# ADC_Sergeant.net
KiCad netlist of a schematic drawn in Altium Designer
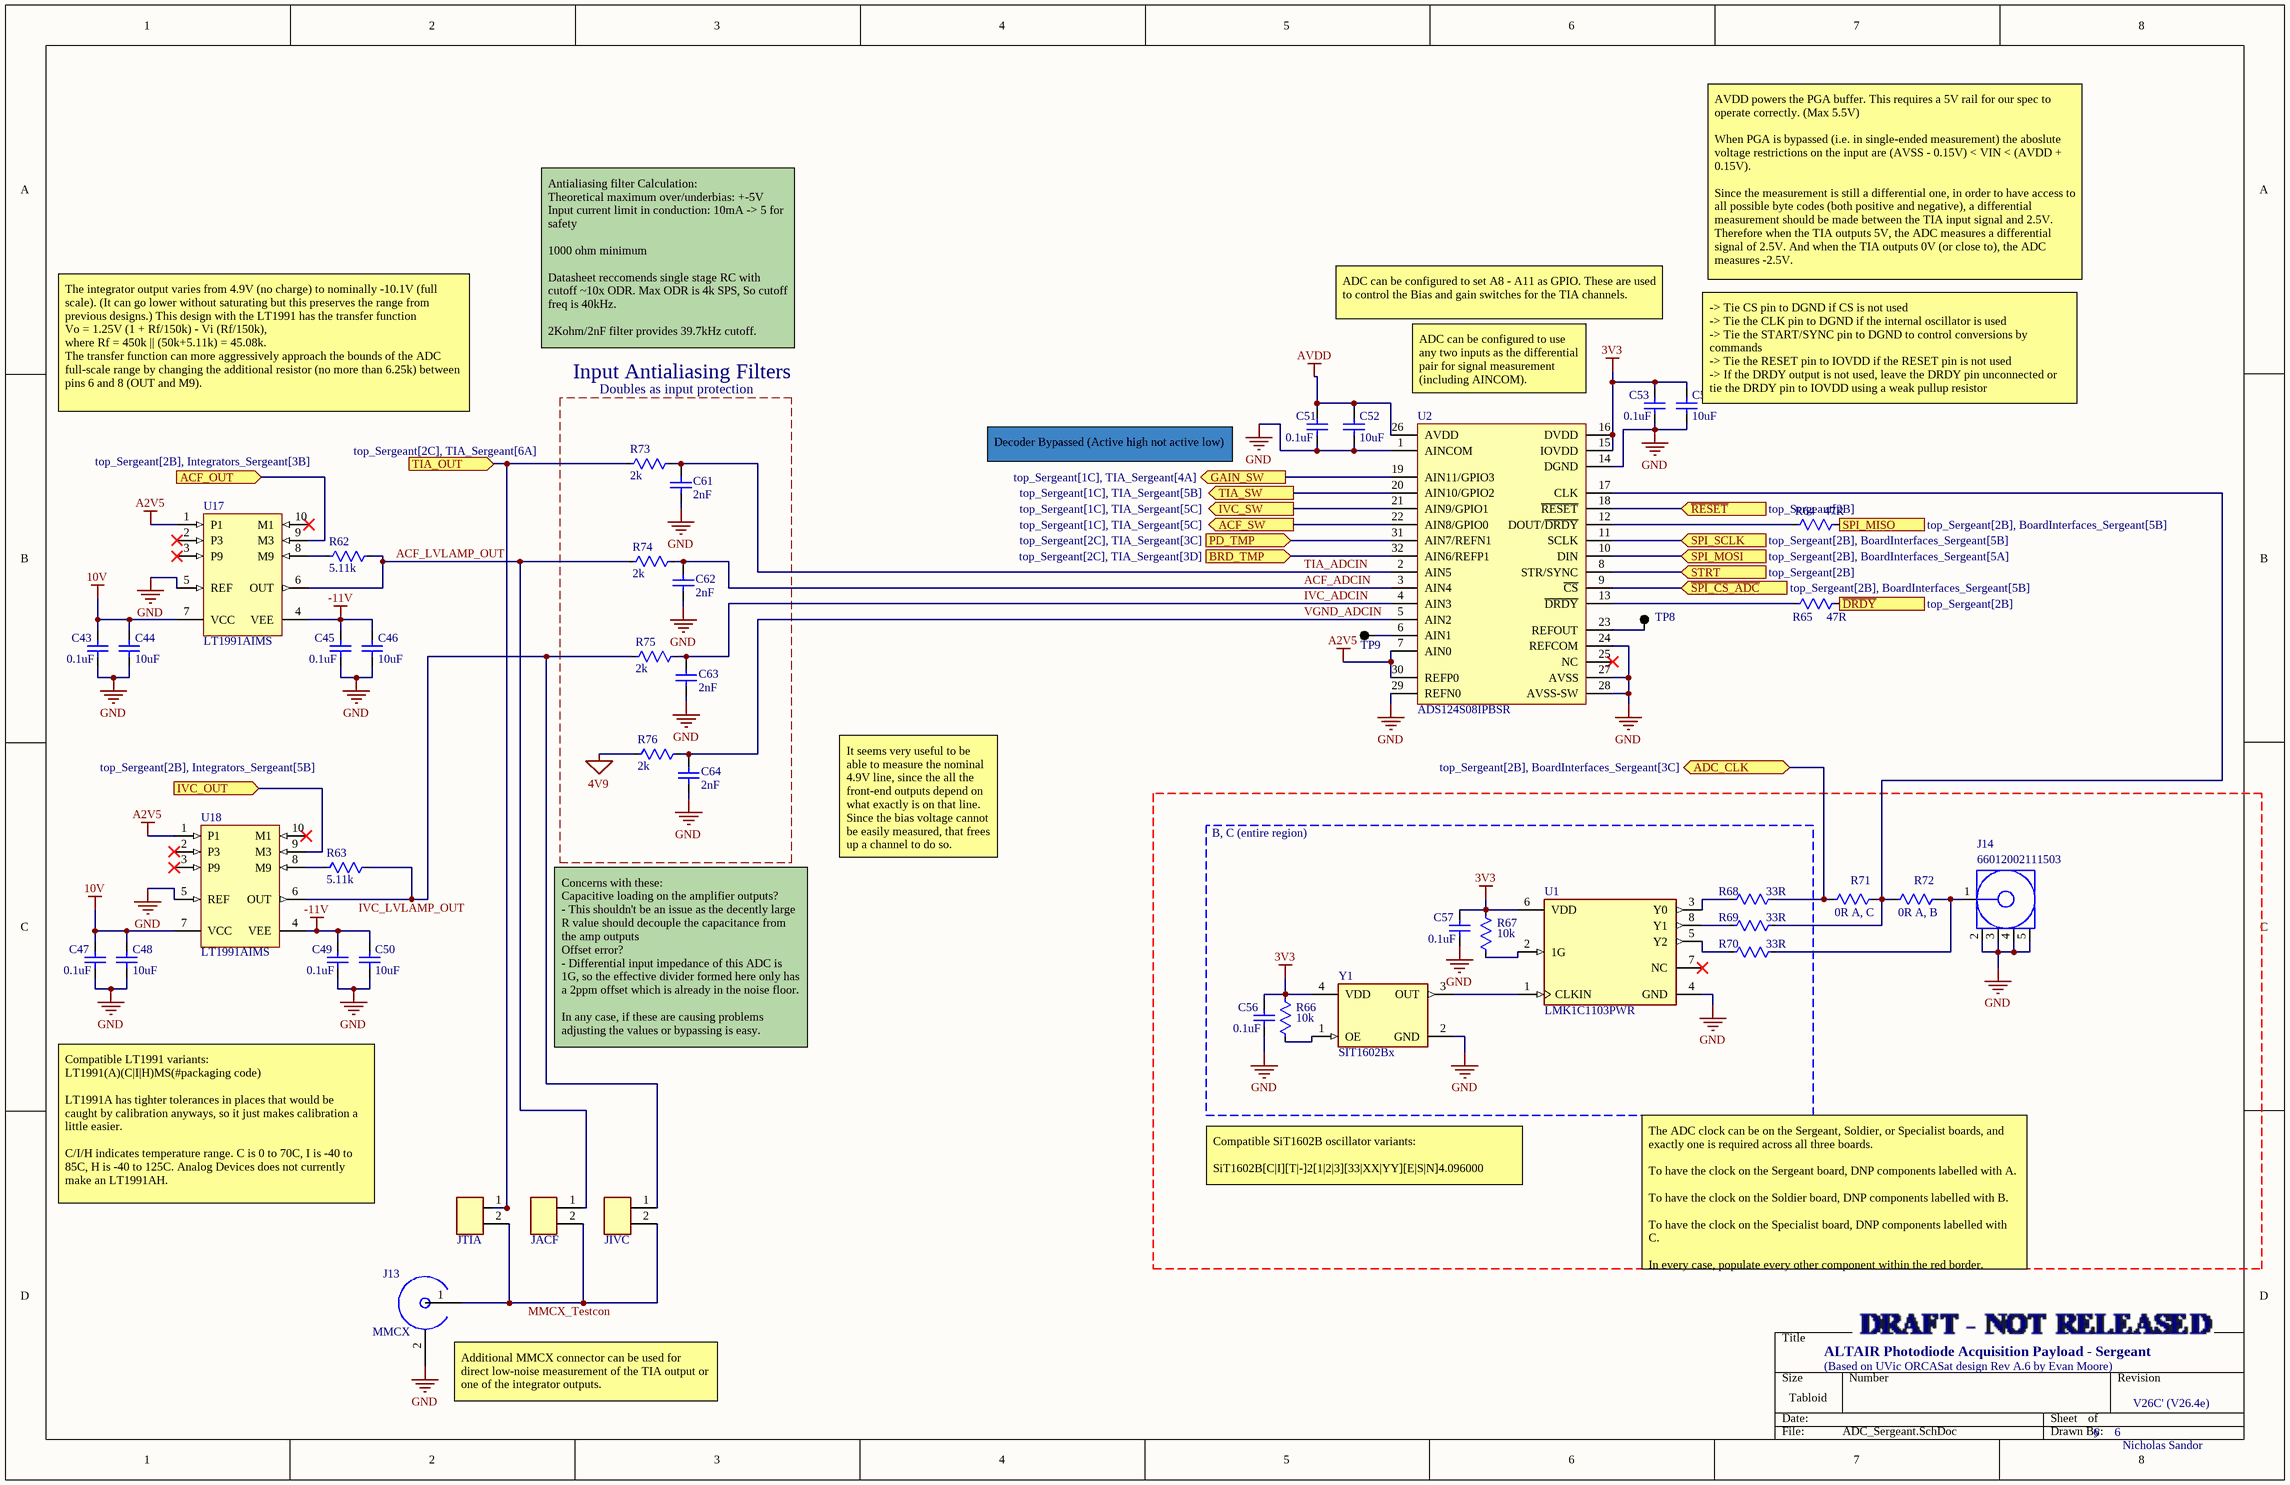
[diagram p0: ADC_Sergeant.SchDoc]

(export (version "E")
  (design (tool "Eeschema 10.0.6"))
  (components
    (comp (ref "C43")
      (value "0.1uF")
      (footprint "CAP 0603 NON-IPC KEMET X7R")
      (description "Kemet C0603C104K5RACAUTO - Cap Ceramic 0.1uF 50V X7R 10% 0603 125C Paper T/R")
      (fields (field (name "MF") "Kemet") (field (name "MP") "C0603C104K5RACAUTO"))
      (libsource (lib "ALTAIR_PD_Capacitors") (part "CAP"))
    )
    (comp (ref "C44")
      (value "10uF")
      (footprint "CAP 0805 IPC MID DENSITY")
      (description "Murata GRM21BR61E106KA73L - Cap Ceramic 10uF 10% 25V X5R 0805")
      (fields (field (name "MF") "Murata") (field (name "MP") "GRM21BR61E106KA73L"))
      (libsource (lib "ALTAIR_PD_Capacitors") (part "CAP"))
    )
    (comp (ref "C45")
      (value "0.1uF")
      (footprint "CAP 0603 NON-IPC KEMET X7R")
      (description "Kemet C0603C104K5RACAUTO - Cap Ceramic 0.1uF 50V X7R 10% 0603 125C Paper T/R")
      (fields (field (name "MF") "Kemet") (field (name "MP") "C0603C104K5RACAUTO"))
      (libsource (lib "ALTAIR_PD_Capacitors") (part "CAP"))
    )
    (comp (ref "C46")
      (value "10uF")
      (footprint "CAP 0805 IPC MID DENSITY")
      (description "Murata GRM21BR61E106KA73L - Cap Ceramic 10uF 10% 25V X5R 0805")
      (fields (field (name "MF") "Murata") (field (name "MP") "GRM21BR61E106KA73L"))
      (libsource (lib "ALTAIR_PD_Capacitors") (part "CAP"))
    )
    (comp (ref "C47")
      (value "0.1uF")
      (footprint "CAP 0603 NON-IPC KEMET X7R")
      (description "Kemet C0603C104K5RACAUTO - Cap Ceramic 0.1uF 50V X7R 10% 0603 125C Paper T/R")
      (fields (field (name "MF") "Kemet") (field (name "MP") "C0603C104K5RACAUTO"))
      (libsource (lib "ALTAIR_PD_Capacitors") (part "CAP"))
    )
    (comp (ref "C48")
      (value "10uF")
      (footprint "CAP 0805 IPC MID DENSITY")
      (description "Murata GRM21BR61E106KA73L - Cap Ceramic 10uF 10% 25V X5R 0805")
      (fields (field (name "MF") "Murata") (field (name "MP") "GRM21BR61E106KA73L"))
      (libsource (lib "ALTAIR_PD_Capacitors") (part "CAP"))
    )
    (comp (ref "C49")
      (value "0.1uF")
      (footprint "CAP 0603 NON-IPC KEMET X7R")
      (description "Kemet C0603C104K5RACAUTO - Cap Ceramic 0.1uF 50V X7R 10% 0603 125C Paper T/R")
      (fields (field (name "MF") "Kemet") (field (name "MP") "C0603C104K5RACAUTO"))
      (libsource (lib "ALTAIR_PD_Capacitors") (part "CAP"))
    )
    (comp (ref "C50")
      (value "10uF")
      (footprint "CAP 0805 IPC MID DENSITY")
      (description "Murata GRM21BR61E106KA73L - Cap Ceramic 10uF 10% 25V X5R 0805")
      (fields (field (name "MF") "Murata") (field (name "MP") "GRM21BR61E106KA73L"))
      (libsource (lib "ALTAIR_PD_Capacitors") (part "CAP"))
    )
    (comp (ref "C51")
      (value "0.1uF")
      (footprint "CAP 0603 IPC MID DENSITY")
      (description "Kemet C0603C104K5RACAUTO - Cap Ceramic 0.1uF 50V X7R 10% 0603 125C Paper T/R")
      (fields (field (name "MF") "Kemet") (field (name "MP") "C0603C104K5RACAUTO"))
      (libsource (lib "ALTAIR_PD_Capacitors") (part "CAP"))
    )
    (comp (ref "C52")
      (value "10uF")
      (footprint "CAP 0805 IPC MID DENSITY")
      (description "Murata GRM21BR61E106KA73L - Cap Ceramic 10uF 10% 25V X5R 0805")
      (fields (field (name "MF") "Murata") (field (name "MP") "GRM21BR61E106KA73L"))
      (libsource (lib "ALTAIR_PD_Capacitors") (part "CAP"))
    )
    (comp (ref "C53")
      (value "0.1uF")
      (footprint "CAP 0603 IPC MID DENSITY")
      (description "Kemet C0603C104K5RACAUTO - Cap Ceramic 0.1uF 50V X7R 10% 0603 125C Paper T/R")
      (fields (field (name "MF") "Kemet") (field (name "MP") "C0603C104K5RACAUTO"))
      (libsource (lib "ALTAIR_PD_Capacitors") (part "CAP"))
    )
    (comp (ref "C54")
      (value "10uF")
      (footprint "CAP 0805 IPC MID DENSITY")
      (description "Murata GRM21BR61E106KA73L - Cap Ceramic 10uF 10% 25V X5R 0805")
      (fields (field (name "MF") "Murata") (field (name "MP") "GRM21BR61E106KA73L"))
      (libsource (lib "ALTAIR_PD_Capacitors") (part "CAP"))
    )
    (comp (ref "C56")
      (value "0.1uF")
      (footprint "CAP 0603 IPC MID DENSITY")
      (description "Kemet C0603C104K5RACAUTO - Cap Ceramic 0.1uF 50V X7R 10% 0603 125C Paper T/R")
      (fields (field (name "MF") "Kemet") (field (name "MP") "C0603C104K5RACAUTO"))
      (libsource (lib "ALTAIR_PD_Capacitors") (part "CAP"))
    )
    (comp (ref "C57")
      (value "0.1uF")
      (footprint "CAP 0603 IPC MID DENSITY")
      (description "Kemet C0603C104K5RACAUTO - Cap Ceramic 0.1uF 50V X7R 10% 0603 125C Paper T/R")
      (fields (field (name "MF") "Kemet") (field (name "MP") "C0603C104K5RACAUTO"))
      (libsource (lib "ALTAIR_PD_Capacitors") (part "CAP"))
    )
    (comp (ref "C61")
      (value "2nF")
      (footprint "CAP 0603 IPC MID DENSITY")
      (description "Murata GCM1885C1H202FA16J 50V 2nF C0G ±1% 0603")
      (fields (field (name "MF") "Murata") (field (name "MP") "GCM1885C1H202FA16J"))
      (libsource (lib "ALTAIR_PD_Capacitors") (part "CAP"))
    )
    (comp (ref "C62")
      (value "2nF")
      (footprint "CAP 0603 IPC MID DENSITY")
      (description "Murata GCM1885C1H202FA16J 50V 2nF C0G ±1% 0603")
      (fields (field (name "MF") "Murata") (field (name "MP") "GCM1885C1H202FA16J"))
      (libsource (lib "ALTAIR_PD_Capacitors") (part "CAP"))
    )
    (comp (ref "C63")
      (value "2nF")
      (footprint "CAP 0603 IPC MID DENSITY")
      (description "Murata GCM1885C1H202FA16J 50V 2nF C0G ±1% 0603")
      (fields (field (name "MF") "Murata") (field (name "MP") "GCM1885C1H202FA16J"))
      (libsource (lib "ALTAIR_PD_Capacitors") (part "CAP"))
    )
    (comp (ref "C64")
      (value "2nF")
      (footprint "CAP 0603 IPC MID DENSITY")
      (description "Murata GCM1885C1H202FA16J 50V 2nF C0G ±1% 0603")
      (fields (field (name "MF") "Murata") (field (name "MP") "GCM1885C1H202FA16J"))
      (libsource (lib "ALTAIR_PD_Capacitors") (part "CAP"))
    )
    (comp (ref "J13")
      (value "MMCX")
      (footprint "COAX MMCX SMD")
      (description "Conn MMCX F 50Ohm Solder ST SMD Gold Tray")
      (fields (field (name "MF") "Molex") (field (name "MP") "0734152061"))
      (libsource (lib "ALTAIR_PD_Coaxial") (part "MMCX_recp"))
    )
    (comp (ref "J14")
      (value "66012002111503")
      (footprint "COAX MMCX THT")
      (description "Rf Coaxial, Mmcx Jack, 50 Ohm, Pcb Rohs Compliant: Yes ¦Wurth Elektronik 66012002111503")
      (fields (field (name "MF") "Wurth Elektronik"))
      (libsource (lib "ALTAIR_PD_Coaxial") (part "CMP-207975-000001-3"))
    )
    (comp (ref "JACF")
      (value "JACF")
      (footprint "ALTAIR_PD_Headers:JUMPER 2POS 1MM PITCH THT")
      (description "2x1 Header THT 1mm Pitch")
      (fields
        (field (name "MF") "GCT (GLOBAL CONNECTOR TECHNOLOGY)")
        (field (name "MP") "BC020-02-A-0200-0300-L-G")
      )
      (libsource (lib "ALTAIR_PD_Headers") (part "BC020-02-A-0200-0300-L-G"))
    )
    (comp (ref "JIVC")
      (value "JIVC")
      (footprint "ALTAIR_PD_Headers:JUMPER 2POS 1MM PITCH THT")
      (description "2x1 Header THT 1mm Pitch")
      (fields
        (field (name "MF") "GCT (GLOBAL CONNECTOR TECHNOLOGY)")
        (field (name "MP") "BC020-02-A-0200-0300-L-G")
      )
      (libsource (lib "ALTAIR_PD_Headers") (part "BC020-02-A-0200-0300-L-G"))
    )
    (comp (ref "JTIA")
      (value "JTIA")
      (footprint "ALTAIR_PD_Headers:JUMPER 2POS 1MM PITCH THT")
      (description "2x1 Header THT 1mm Pitch")
      (fields
        (field (name "MF") "GCT (GLOBAL CONNECTOR TECHNOLOGY)")
        (field (name "MP") "BC020-02-A-0200-0300-L-G")
      )
      (libsource (lib "ALTAIR_PD_Headers") (part "BC020-02-A-0200-0300-L-G"))
    )
    (comp (ref "R62")
      (value "5.11k")
      (footprint "RES 0402 IPC MID DENSITY")
      (description "Panasonic ERA-2AEB5111X - Res 5.11k 0.1% 1/16W SMD 0402")
      (fields (field (name "MF") "Panasonic Electronic Components") (field (name "MP") "ERA-2AEB5111X"))
      (libsource (lib "ALTAIR_PD_Resistors") (part "RES"))
    )
    (comp (ref "R63")
      (value "5.11k")
      (footprint "RES 0402 IPC MID DENSITY")
      (description "Panasonic ERA-2AEB5111X - Res 5.11k 0.1% 1/16W SMD 0402")
      (fields (field (name "MF") "Panasonic Electronic Components") (field (name "MP") "ERA-2AEB5111X"))
      (libsource (lib "ALTAIR_PD_Resistors") (part "RES"))
    )
    (comp (ref "R64")
      (value "47R")
      (footprint "RES 0402 NON-IPC SEI")
      (description "Stackpole RMCF0402JT47R0 - Res 47Ohm 5% 0.063W 0402 Thick Film AEC-Q200 compliant")
      (fields (field (name "MF") "Stackpole Electronics Inc.") (field (name "MP") "RMCF0402JT47R0"))
      (libsource (lib "ALTAIR_PD_Resistors") (part "RES"))
    )
    (comp (ref "R65")
      (value "47R")
      (footprint "RES 0402 NON-IPC SEI")
      (description "Stackpole RMCF0402JT47R0 - Res 47Ohm 5% 0.063W 0402 Thick Film AEC-Q200 compliant")
      (fields (field (name "MF") "Stackpole Electronics Inc.") (field (name "MP") "RMCF0402JT47R0"))
      (libsource (lib "ALTAIR_PD_Resistors") (part "RES"))
    )
    (comp (ref "R66")
      (value "10k")
      (footprint "RES 0603 IPC MID DENSITY")
      (description "Vishay CRCW060310K0FKEA SMD 0603 10k, CRCW e3 Series, 75V, thick film, 100mW")
      (fields (field (name "MF") "Vishay Dale") (field (name "MP") "CRCW060310K0FKEA"))
      (libsource (lib "ALTAIR_PD_Resistors") (part "RES"))
    )
    (comp (ref "R67")
      (value "10k")
      (footprint "RES 0603 IPC MID DENSITY")
      (description "Vishay CRCW060310K0FKEA SMD 0603 10k, CRCW e3 Series, 75V, thick film, 100mW")
      (fields (field (name "MF") "Vishay Dale") (field (name "MP") "CRCW060310K0FKEA"))
      (libsource (lib "ALTAIR_PD_Resistors") (part "RES"))
    )
    (comp (ref "R68")
      (value "33R")
      (footprint "RES 0402 NON-IPC YAGEO")
      (description "Yageo RC0402FR-0733RL - Res 33Ohm 1% 1/16W 0402")
      (fields (field (name "MF") "YAGEO") (field (name "MP") "RC0402FR-0733RL"))
      (libsource (lib "ALTAIR_PD_Resistors") (part "RES"))
    )
    (comp (ref "R69")
      (value "33R")
      (footprint "RES 0402 NON-IPC YAGEO")
      (description "Yageo RC0402FR-0733RL - Res 33Ohm 1% 1/16W 0402")
      (fields (field (name "MF") "YAGEO") (field (name "MP") "RC0402FR-0733RL"))
      (libsource (lib "ALTAIR_PD_Resistors") (part "RES"))
    )
    (comp (ref "R70")
      (value "33R")
      (footprint "RES 0402 NON-IPC YAGEO")
      (description "Yageo RC0402FR-0733RL - Res 33Ohm 1% 1/16W 0402")
      (fields (field (name "MF") "YAGEO") (field (name "MP") "RC0402FR-0733RL"))
      (libsource (lib "ALTAIR_PD_Resistors") (part "RES"))
    )
    (comp (ref "R71")
      (value "0R A, C")
      (footprint "RES 0402 IPC MID DENSITY")
      (description "Yageo RC0402JR-070RL - Res 0 Ohms 1/16W SMD 0402")
      (fields (field (name "MF") "YAGEO") (field (name "MP") "RC0402JR-070RL"))
      (libsource (lib "ALTAIR_PD_Resistors") (part "RES"))
    )
    (comp (ref "R72")
      (value "0R A, B")
      (footprint "RES 0402 IPC MID DENSITY")
      (description "Yageo RC0402JR-070RL - Res 0 Ohms 1/16W SMD 0402")
      (fields (field (name "MF") "YAGEO") (field (name "MP") "RC0402JR-070RL"))
      (libsource (lib "ALTAIR_PD_Resistors") (part "RES"))
    )
    (comp (ref "R73")
      (value "2k")
      (footprint "RES 0603 IPC MID DENSITY")
      (description "Panasonic ERJ-3EKF2001V Res Thick Film 0603 2K Ohm 1% 1/10W ±100ppm/°C")
      (fields (field (name "MF") "Panasonic Electronic Components") (field (name "MP") "ERJ-3EKF2001V"))
      (libsource (lib "ALTAIR_PD_Resistors") (part "RES"))
    )
    (comp (ref "R74")
      (value "2k")
      (footprint "RES 0603 IPC MID DENSITY")
      (description "Panasonic ERJ-3EKF2001V Res Thick Film 0603 2K Ohm 1% 1/10W ±100ppm/°C")
      (fields (field (name "MF") "Panasonic Electronic Components") (field (name "MP") "ERJ-3EKF2001V"))
      (libsource (lib "ALTAIR_PD_Resistors") (part "RES"))
    )
    (comp (ref "R75")
      (value "2k")
      (footprint "RES 0603 IPC MID DENSITY")
      (description "Panasonic ERJ-3EKF2001V Res Thick Film 0603 2K Ohm 1% 1/10W ±100ppm/°C")
      (fields (field (name "MF") "Panasonic Electronic Components") (field (name "MP") "ERJ-3EKF2001V"))
      (libsource (lib "ALTAIR_PD_Resistors") (part "RES"))
    )
    (comp (ref "R76")
      (value "2k")
      (footprint "RES 0603 IPC MID DENSITY")
      (description "Panasonic ERJ-3EKF2001V Res Thick Film 0603 2K Ohm 1% 1/10W ±100ppm/°C")
      (fields (field (name "MF") "Panasonic Electronic Components") (field (name "MP") "ERJ-3EKF2001V"))
      (libsource (lib "ALTAIR_PD_Resistors") (part "RES"))
    )
    (comp (ref "TP8")
      (value "Testpoint")
      (footprint "TESTPOINT THT")
      (libsource (lib "ALTAIR_PD_Testpoint") (part "Testpoint"))
    )
    (comp (ref "TP9")
      (value "Testpoint")
      (footprint "TESTPOINT THT")
      (libsource (lib "ALTAIR_PD_Testpoint") (part "Testpoint"))
    )
    (comp (ref "U1")
      (value "LMK1C1103PWR")
      (footprint "8-TSSOP 0.65MM PITCH 4.4MM WIDTH IPC MID DENSITY")
      (description "LVCMOS CLOCK BUFFER 3-CHANNEL")
      (fields (field (name "MF") "Texas Instruments"))
      (libsource (lib "ALTAIR_PD_ClockParts") (part "LMK1C1103PWR"))
    )
    (comp (ref "U2")
      (value "ADS124S08IPBSR")
      (footprint "32TQFP 7X7MM IPC LOW DENSITY")
      (description "24BIT ADC Delta-Sigma 4k samples/s PGA V-reference")
      (fields (field (name "MF") "Texas Instruments"))
      (libsource (lib "ALTAIR_PD_ADCs") (part "ADS124S08IPBSR"))
    )
    (comp (ref "U17")
      (value "LT1991AIMS")
      (footprint "10-SOP 0.5MM PITCH 3MM WIDTH IPC HIGH DENSITY")
      (fields
        (field (name "MF") "Linear Technology")
        (field (name "MP") "LT1991AIMS#PBF")
        (field (name "LINEAR TECHNOLOGY PART NUMBER") "LT1991")
      )
      (libsource (lib "ALTAIR_PD_Amplifiers") (part "LT1991IMS#TRPBF"))
    )
    (comp (ref "U18")
      (value "LT1991AIMS")
      (footprint "10-SOP 0.5MM PITCH 3MM WIDTH IPC HIGH DENSITY")
      (fields
        (field (name "MF") "Linear Technology")
        (field (name "MP") "LT1991AIMS#PBF")
        (field (name "LINEAR TECHNOLOGY PART NUMBER") "LT1991")
      )
      (libsource (lib "ALTAIR_PD_Amplifiers") (part "LT1991IMS#TRPBF"))
    )
    (comp (ref "Y1")
      (value "SIT1602Bx")
      (footprint "4PQFN NON-IPC SITIME")
      (description "MEMS OSC XO 4.096MHZ H/LVCMOS")
      (fields (field (name "MF") "SiTime") (field (name "MP") "SiT1602BC-21-XXN-4.096000"))
      (libsource (lib "ALTAIR_PD_ClockParts") (part "SIT1602Bx"))
    )
  )
  (nets
    (net (code "1") (name "-11V") (class "Default")
      (node (ref "C45") (pin "2") (pinfunction "2_2") (pintype "passive"))
      (node (ref "C46") (pin "2") (pinfunction "2_2") (pintype "passive"))
      (node (ref "C49") (pin "2") (pinfunction "2_2") (pintype "passive"))
      (node (ref "C50") (pin "2") (pinfunction "2_2") (pintype "passive"))
      (node (ref "U17") (pin "4") (pinfunction "VEE_4") (pintype "power_in"))
      (node (ref "U18") (pin "4") (pinfunction "VEE_4") (pintype "power_in"))
    )
    (net (code "2") (name "/ACF_ADCIN") (class "Default")
      (node (ref "C62") (pin "2") (pinfunction "2_2") (pintype "passive"))
      (node (ref "R74") (pin "2") (pinfunction "2_2") (pintype "passive"))
      (node (ref "U2") (pin "3") (pinfunction "AIN4_3") (pintype "passive"))
    )
    (net (code "3") (name "/ACF_LVLAMP_OUT") (class "Default")
      (node (ref "JACF") (pin "1") (pinfunction "1_1") (pintype "passive"))
      (node (ref "R62") (pin "2") (pinfunction "2_2") (pintype "passive"))
      (node (ref "R74") (pin "1") (pinfunction "1_1") (pintype "passive"))
      (node (ref "U17") (pin "6") (pinfunction "OUT_6") (pintype "output"))
    )
    (net (code "4") (name "/ACF_OUT") (class "Default")
      (node (ref "U17") (pin "9") (pinfunction "M3_9") (pintype "input"))
    )
    (net (code "5") (name "/ACF_SW") (class "Default")
      (node (ref "U2") (pin "22") (pinfunction "AIN8/GPIO0_22") (pintype "passive"))
    )
    (net (code "6") (name "/ADC_CLK") (class "Default")
      (node (ref "R68") (pin "1") (pinfunction "1_1") (pintype "passive"))
      (node (ref "R71") (pin "2") (pinfunction "2_2") (pintype "passive"))
    )
    (net (code "7") (name "/BRD_TMP") (class "Default")
      (node (ref "U2") (pin "32") (pinfunction "AIN6/REFP1_32") (pintype "passive"))
    )
    (net (code "8") (name "/DRDY") (class "Default")
      (node (ref "R65") (pin "2") (pinfunction "2_2") (pintype "passive"))
    )
    (net (code "9") (name "/GAIN_SW") (class "Default")
      (node (ref "U2") (pin "19") (pinfunction "AIN11/GPIO3_19") (pintype "passive"))
    )
    (net (code "10") (name "/IVC_ADCIN") (class "Default")
      (node (ref "C63") (pin "2") (pinfunction "2_2") (pintype "passive"))
      (node (ref "R75") (pin "2") (pinfunction "2_2") (pintype "passive"))
      (node (ref "U2") (pin "4") (pinfunction "AIN3_4") (pintype "passive"))
    )
    (net (code "11") (name "/IVC_LVLAMP_OUT") (class "Default")
      (node (ref "JIVC") (pin "1") (pinfunction "1_1") (pintype "passive"))
      (node (ref "R63") (pin "2") (pinfunction "2_2") (pintype "passive"))
      (node (ref "R75") (pin "1") (pinfunction "1_1") (pintype "passive"))
      (node (ref "U18") (pin "6") (pinfunction "OUT_6") (pintype "output"))
    )
    (net (code "12") (name "/IVC_OUT") (class "Default")
      (node (ref "U18") (pin "9") (pinfunction "M3_9") (pintype "input"))
    )
    (net (code "13") (name "/IVC_SW") (class "Default")
      (node (ref "U2") (pin "21") (pinfunction "AIN9/GPIO1_21") (pintype "passive"))
    )
    (net (code "14") (name "/MMCX_Testcon") (class "Default")
      (node (ref "J13") (pin "1") (pinfunction "1_1") (pintype "passive"))
      (node (ref "JACF") (pin "2") (pinfunction "2_2") (pintype "passive"))
      (node (ref "JIVC") (pin "2") (pinfunction "2_2") (pintype "passive"))
      (node (ref "JTIA") (pin "2") (pinfunction "2_2") (pintype "passive"))
    )
    (net (code "15") (name "/PD_TMP") (class "Default")
      (node (ref "U2") (pin "31") (pinfunction "AIN7/REFN1_31") (pintype "passive"))
    )
    (net (code "16") (name "/RESET") (class "Default")
      (node (ref "U2") (pin "18") (pinfunction "~{RESET}_18") (pintype "passive"))
    )
    (net (code "17") (name "/SPI_CS_ADC") (class "Default")
      (node (ref "U2") (pin "9") (pinfunction "~{CS}_9") (pintype "passive"))
    )
    (net (code "18") (name "/SPI_MISO") (class "Default")
      (node (ref "R64") (pin "2") (pinfunction "2_2") (pintype "passive"))
    )
    (net (code "19") (name "/SPI_MOSI") (class "Default")
      (node (ref "U2") (pin "10") (pinfunction "DIN_10") (pintype "passive"))
    )
    (net (code "20") (name "/SPI_SCLK") (class "Default")
      (node (ref "U2") (pin "11") (pinfunction "SCLK_11") (pintype "passive"))
    )
    (net (code "21") (name "/STRT") (class "Default")
      (node (ref "U2") (pin "8") (pinfunction "STR/SYNC_8") (pintype "passive"))
    )
    (net (code "22") (name "/TIA_ADCIN") (class "Default")
      (node (ref "C61") (pin "2") (pinfunction "2_2") (pintype "passive"))
      (node (ref "R73") (pin "2") (pinfunction "2_2") (pintype "passive"))
      (node (ref "U2") (pin "2") (pinfunction "AIN5_2") (pintype "passive"))
    )
    (net (code "23") (name "/TIA_OUT") (class "Default")
      (node (ref "JTIA") (pin "1") (pinfunction "1_1") (pintype "passive"))
      (node (ref "R73") (pin "1") (pinfunction "1_1") (pintype "passive"))
    )
    (net (code "24") (name "/TIA_SW") (class "Default")
      (node (ref "U2") (pin "20") (pinfunction "AIN10/GPIO2_20") (pintype "passive"))
    )
    (net (code "25") (name "/VGND_ADCIN") (class "Default")
      (node (ref "C64") (pin "2") (pinfunction "2_2") (pintype "passive"))
      (node (ref "R76") (pin "2") (pinfunction "2_2") (pintype "passive"))
      (node (ref "U2") (pin "5") (pinfunction "AIN2_5") (pintype "passive"))
    )
    (net (code "26") (name "3V3") (class "Default")
      (node (ref "C53") (pin "2") (pinfunction "2_2") (pintype "passive"))
      (node (ref "C54") (pin "2") (pinfunction "2_2") (pintype "passive"))
      (node (ref "C56") (pin "2") (pinfunction "2_2") (pintype "passive"))
      (node (ref "C57") (pin "2") (pinfunction "2_2") (pintype "passive"))
      (node (ref "R66") (pin "2") (pinfunction "2_2") (pintype "passive"))
      (node (ref "R67") (pin "2") (pinfunction "2_2") (pintype "passive"))
      (node (ref "U1") (pin "6") (pinfunction "VDD_6") (pintype "power_in"))
      (node (ref "U2") (pin "15") (pinfunction "IOVDD_15") (pintype "passive"))
      (node (ref "U2") (pin "16") (pinfunction "DVDD_16") (pintype "passive"))
      (node (ref "Y1") (pin "4") (pinfunction "VDD_4") (pintype "power_in"))
    )
    (net (code "27") (name "4V9") (class "Default")
      (node (ref "R76") (pin "1") (pinfunction "1_1") (pintype "passive"))
    )
    (net (code "28") (name "10V") (class "Default")
      (node (ref "C43") (pin "2") (pinfunction "2_2") (pintype "passive"))
      (node (ref "C44") (pin "2") (pinfunction "2_2") (pintype "passive"))
      (node (ref "C47") (pin "2") (pinfunction "2_2") (pintype "passive"))
      (node (ref "C48") (pin "2") (pinfunction "2_2") (pintype "passive"))
      (node (ref "U17") (pin "7") (pinfunction "VCC_7") (pintype "power_in"))
      (node (ref "U18") (pin "7") (pinfunction "VCC_7") (pintype "power_in"))
    )
    (net (code "29") (name "A2V5") (class "Default")
      (node (ref "U17") (pin "1") (pinfunction "P1_1") (pintype "input"))
      (node (ref "U18") (pin "1") (pinfunction "P1_1") (pintype "input"))
      (node (ref "U2") (pin "30") (pinfunction "REFP0_30") (pintype "passive"))
      (node (ref "U2") (pin "7") (pinfunction "AIN0_7") (pintype "passive"))
    )
    (net (code "30") (name "AVDD") (class "Default")
      (node (ref "C51") (pin "2") (pinfunction "2_2") (pintype "passive"))
      (node (ref "C52") (pin "2") (pinfunction "2_2") (pintype "passive"))
      (node (ref "U2") (pin "26") (pinfunction "AVDD_26") (pintype "passive"))
    )
    (net (code "31") (name "GND") (class "Default")
      (node (ref "C43") (pin "1") (pinfunction "1_1") (pintype "passive"))
      (node (ref "C44") (pin "1") (pinfunction "1_1") (pintype "passive"))
      (node (ref "C45") (pin "1") (pinfunction "1_1") (pintype "passive"))
      (node (ref "C46") (pin "1") (pinfunction "1_1") (pintype "passive"))
      (node (ref "C47") (pin "1") (pinfunction "1_1") (pintype "passive"))
      (node (ref "C48") (pin "1") (pinfunction "1_1") (pintype "passive"))
      (node (ref "C49") (pin "1") (pinfunction "1_1") (pintype "passive"))
      (node (ref "C50") (pin "1") (pinfunction "1_1") (pintype "passive"))
      (node (ref "C51") (pin "1") (pinfunction "1_1") (pintype "passive"))
      (node (ref "C52") (pin "1") (pinfunction "1_1") (pintype "passive"))
      (node (ref "C53") (pin "1") (pinfunction "1_1") (pintype "passive"))
      (node (ref "C54") (pin "1") (pinfunction "1_1") (pintype "passive"))
      (node (ref "C56") (pin "1") (pinfunction "1_1") (pintype "passive"))
      (node (ref "C57") (pin "1") (pinfunction "1_1") (pintype "passive"))
      (node (ref "C61") (pin "1") (pinfunction "1_1") (pintype "passive"))
      (node (ref "C62") (pin "1") (pinfunction "1_1") (pintype "passive"))
      (node (ref "C63") (pin "1") (pinfunction "1_1") (pintype "passive"))
      (node (ref "C64") (pin "1") (pinfunction "1_1") (pintype "passive"))
      (node (ref "J13") (pin "2") (pinfunction "2_2") (pintype "passive"))
      (node (ref "J14") (pin "2") (pinfunction "GND_2") (pintype "passive"))
      (node (ref "J14") (pin "3") (pinfunction "GND_3") (pintype "passive"))
      (node (ref "J14") (pin "4") (pinfunction "GND_4") (pintype "passive"))
      (node (ref "J14") (pin "5") (pinfunction "GND_5") (pintype "passive"))
      (node (ref "U1") (pin "4") (pinfunction "GND_4") (pintype "power_in"))
      (node (ref "U17") (pin "5") (pinfunction "REF_5") (pintype "input"))
      (node (ref "U18") (pin "5") (pinfunction "REF_5") (pintype "input"))
      (node (ref "U2") (pin "1") (pinfunction "AINCOM_1") (pintype "passive"))
      (node (ref "U2") (pin "14") (pinfunction "DGND_14") (pintype "passive"))
      (node (ref "U2") (pin "24") (pinfunction "REFCOM_24") (pintype "passive"))
      (node (ref "U2") (pin "27") (pinfunction "AVSS_27") (pintype "passive"))
      (node (ref "U2") (pin "28") (pinfunction "AVSS-SW_28") (pintype "passive"))
      (node (ref "U2") (pin "29") (pinfunction "REFN0_29") (pintype "passive"))
      (node (ref "Y1") (pin "2") (pinfunction "GND_2") (pintype "power_in"))
    )
    (net (code "32") (name "Net-(J14-Signal)") (class "Default")
      (node (ref "J14") (pin "1") (pinfunction "Signal_1") (pintype "passive"))
      (node (ref "R70") (pin "1") (pinfunction "1_1") (pintype "passive"))
      (node (ref "R72") (pin "1") (pinfunction "1_1") (pintype "passive"))
    )
    (net (code "33") (name "Net-(U1-1G)") (class "Default")
      (node (ref "R67") (pin "1") (pinfunction "1_1") (pintype "passive"))
      (node (ref "U1") (pin "2") (pinfunction "1G_2") (pintype "input"))
    )
    (net (code "34") (name "Net-(U1-CLKIN)") (class "Default")
      (node (ref "U1") (pin "1") (pinfunction "CLKIN_1") (pintype "input"))
      (node (ref "Y1") (pin "3") (pinfunction "OUT_3") (pintype "output"))
    )
    (net (code "35") (name "Net-(U1-Y0)") (class "Default")
      (node (ref "R68") (pin "2") (pinfunction "2_2") (pintype "passive"))
      (node (ref "U1") (pin "3") (pinfunction "Y0_3") (pintype "output"))
    )
    (net (code "36") (name "Net-(U1-Y1)") (class "Default")
      (node (ref "R69") (pin "2") (pinfunction "2_2") (pintype "passive"))
      (node (ref "U1") (pin "8") (pinfunction "Y1_8") (pintype "output"))
    )
    (net (code "37") (name "Net-(U1-Y2)") (class "Default")
      (node (ref "R70") (pin "2") (pinfunction "2_2") (pintype "passive"))
      (node (ref "U1") (pin "5") (pinfunction "Y2_5") (pintype "output"))
    )
    (net (code "38") (name "Net-(U2-AIN1)") (class "Default")
      (node (ref "TP9") (pin "1") (pinfunction "1_1") (pintype "passive"))
      (node (ref "U2") (pin "6") (pinfunction "AIN1_6") (pintype "passive"))
    )
    (net (code "39") (name "Net-(U2-CLK)") (class "Default")
      (node (ref "R69") (pin "1") (pinfunction "1_1") (pintype "passive"))
      (node (ref "R71") (pin "1") (pinfunction "1_1") (pintype "passive"))
      (node (ref "R72") (pin "2") (pinfunction "2_2") (pintype "passive"))
      (node (ref "U2") (pin "17") (pinfunction "CLK_17") (pintype "passive"))
    )
    (net (code "40") (name "Net-(U2-DOUT{slash}~{DRDY})") (class "Default")
      (node (ref "R64") (pin "1") (pinfunction "1_1") (pintype "passive"))
      (node (ref "U2") (pin "12") (pinfunction "DOUT/~{DRDY}_12") (pintype "passive"))
    )
    (net (code "41") (name "Net-(U2-REFOUT)") (class "Default")
      (node (ref "TP8") (pin "1") (pinfunction "1_1") (pintype "passive"))
      (node (ref "U2") (pin "23") (pinfunction "REFOUT_23") (pintype "passive"))
    )
    (net (code "42") (name "Net-(U2-~{DRDY})") (class "Default")
      (node (ref "R65") (pin "1") (pinfunction "1_1") (pintype "passive"))
      (node (ref "U2") (pin "13") (pinfunction "~{DRDY}_13") (pintype "passive"))
    )
    (net (code "43") (name "Net-(U17-M9)") (class "Default")
      (node (ref "R62") (pin "1") (pinfunction "1_1") (pintype "passive"))
      (node (ref "U17") (pin "8") (pinfunction "M9_8") (pintype "input"))
    )
    (net (code "44") (name "Net-(U18-M9)") (class "Default")
      (node (ref "R63") (pin "1") (pinfunction "1_1") (pintype "passive"))
      (node (ref "U18") (pin "8") (pinfunction "M9_8") (pintype "input"))
    )
    (net (code "45") (name "Net-(Y1-OE)") (class "Default")
      (node (ref "R66") (pin "1") (pinfunction "1_1") (pintype "passive"))
      (node (ref "Y1") (pin "1") (pinfunction "OE_1") (pintype "input"))
    )
    (net (code "46") (name "unconnected-(U1-NC-Pad7)") (class "Default")
      (node (ref "U1") (pin "7") (pinfunction "NC_7") (pintype "passive+no_connect"))
    )
    (net (code "47") (name "unconnected-(U2-NC-Pad25)") (class "Default")
      (node (ref "U2") (pin "25") (pinfunction "NC_25") (pintype "passive+no_connect"))
    )
    (net (code "48") (name "unconnected-(U17-M1-Pad10)") (class "Default")
      (node (ref "U17") (pin "10") (pinfunction "M1_10") (pintype "input+no_connect"))
    )
    (net (code "49") (name "unconnected-(U17-P3-Pad2)") (class "Default")
      (node (ref "U17") (pin "2") (pinfunction "P3_2") (pintype "input+no_connect"))
    )
    (net (code "50") (name "unconnected-(U17-P9-Pad3)") (class "Default")
      (node (ref "U17") (pin "3") (pinfunction "P9_3") (pintype "input+no_connect"))
    )
    (net (code "51") (name "unconnected-(U18-M1-Pad10)") (class "Default")
      (node (ref "U18") (pin "10") (pinfunction "M1_10") (pintype "input+no_connect"))
    )
    (net (code "52") (name "unconnected-(U18-P3-Pad2)") (class "Default")
      (node (ref "U18") (pin "2") (pinfunction "P3_2") (pintype "input+no_connect"))
    )
    (net (code "53") (name "unconnected-(U18-P9-Pad3)") (class "Default")
      (node (ref "U18") (pin "3") (pinfunction "P9_3") (pintype "input+no_connect"))
    )
  )
)
